# ESP32.net
KiCad netlist of a schematic drawn in Altium Designer
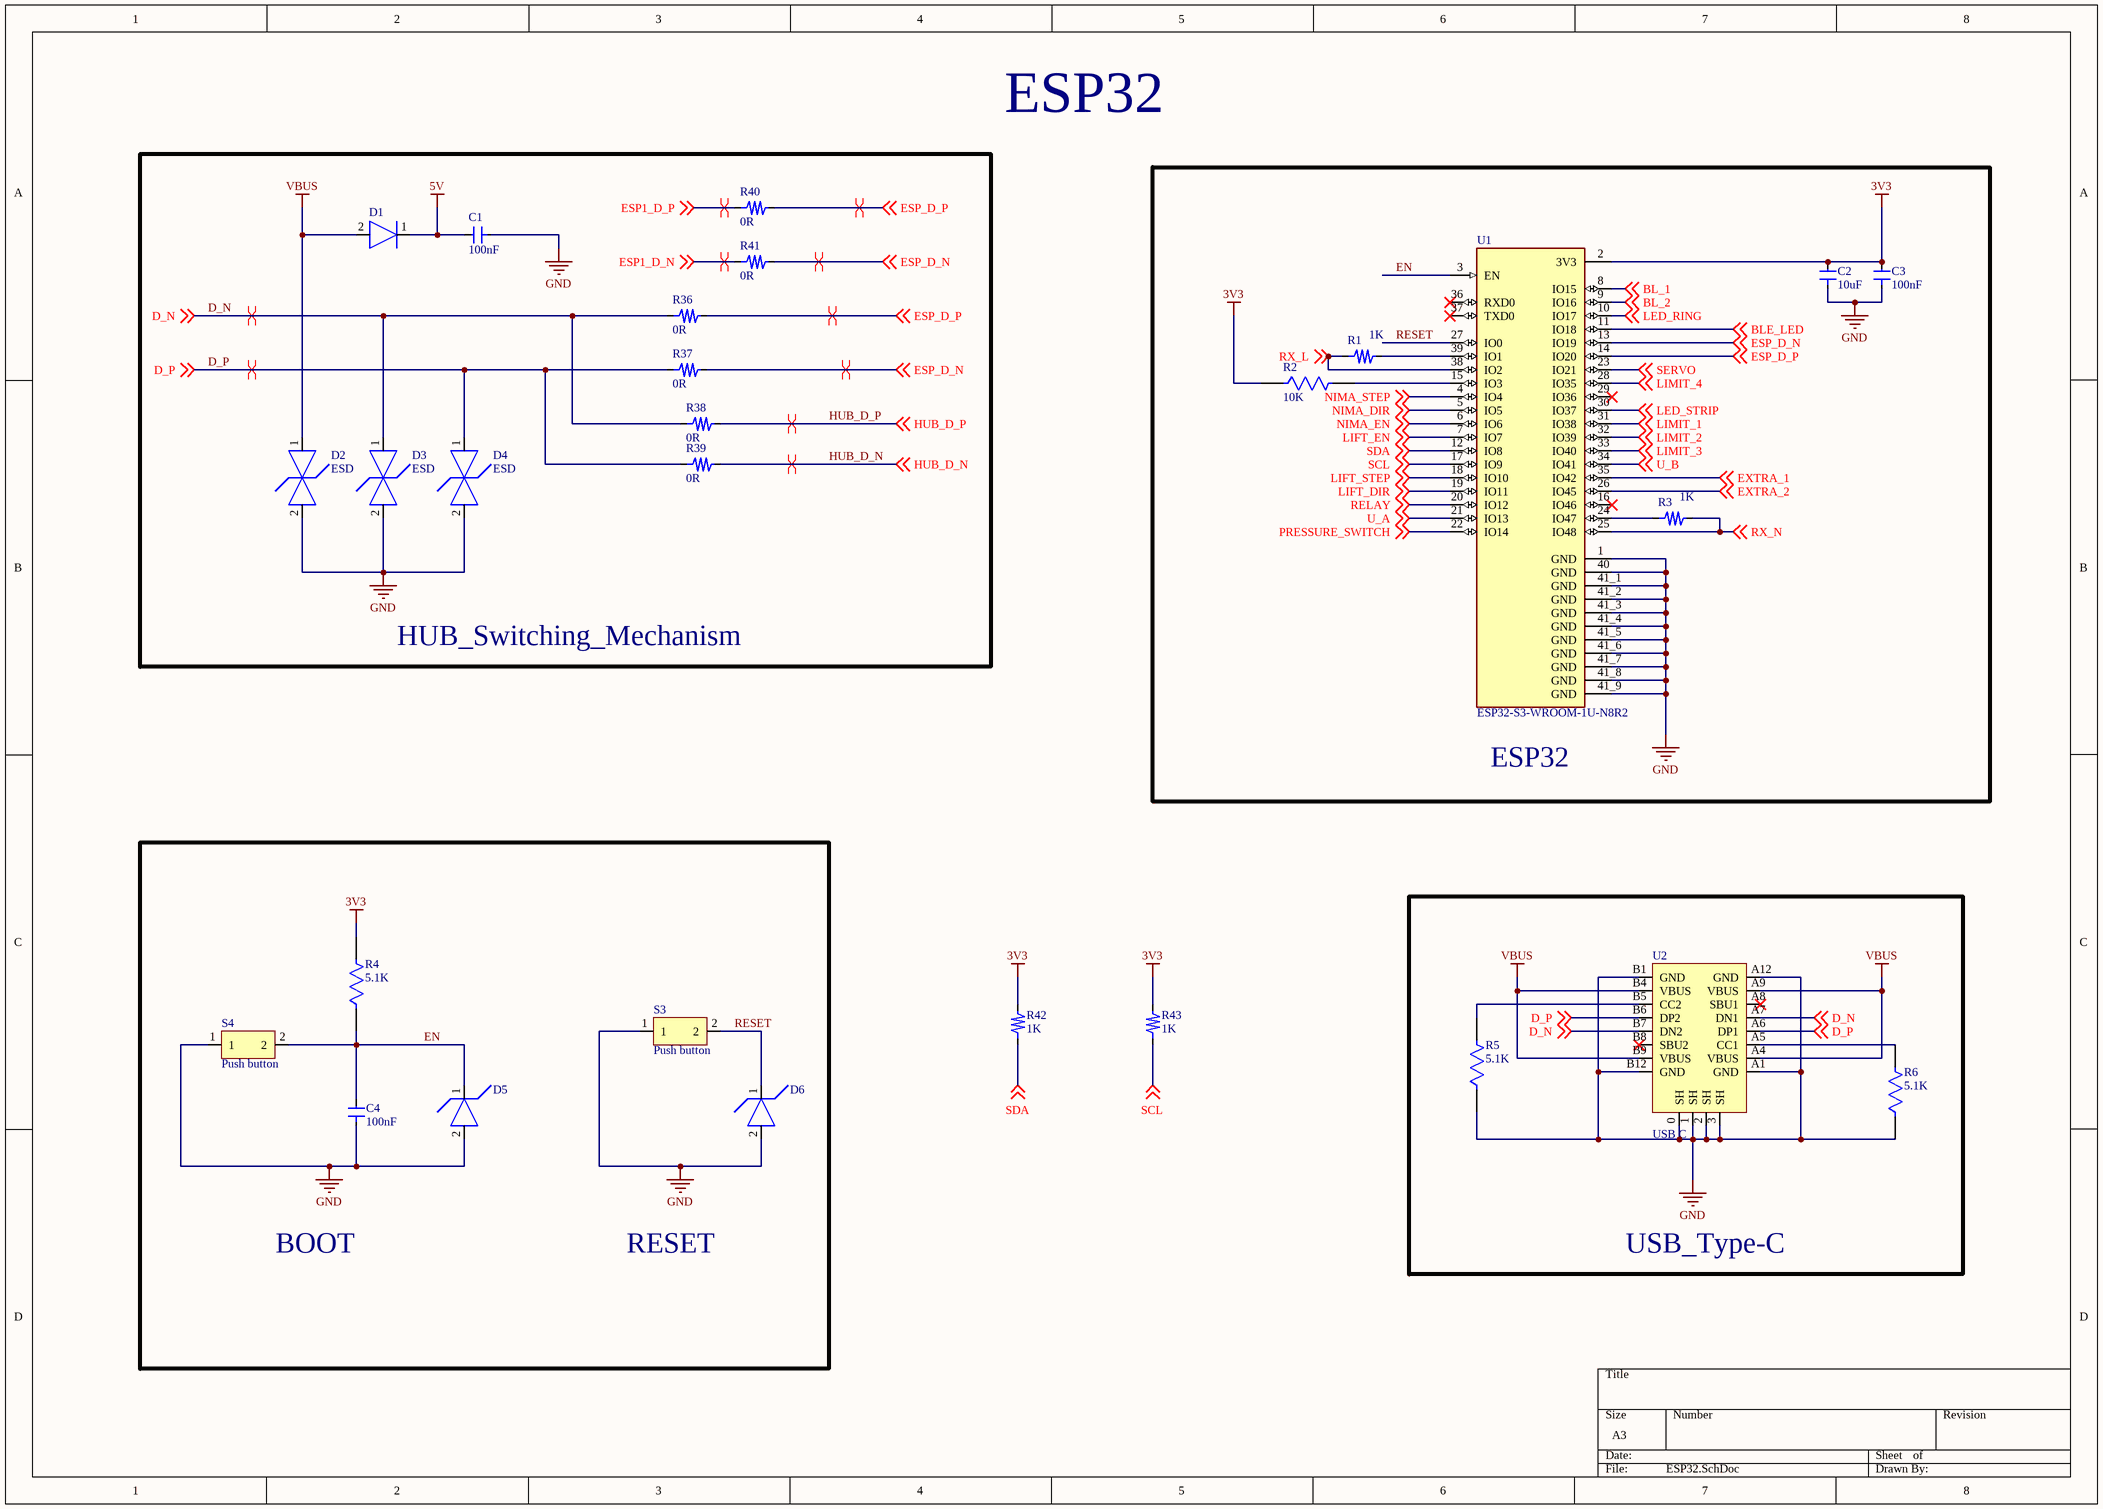
[diagram p0: ESP32.SchDoc]

(export (version "E")
  (design (tool "Eeschema 10.0.6"))
  (components
    (comp (ref "C1")
      (value "100nF")
      (footprint "CAP 0603")
      (fields (field (name "PART NUMBER") "CC0603JRX7R9BB104"))
      (libsource (lib "Schlib2") (part "Capasitor"))
    )
    (comp (ref "C2")
      (value "10uF")
      (footprint "CAP 0603")
      (fields (field (name "PART NUMBER") "CC0603KRX5R5BB106"))
      (libsource (lib "Schlib2") (part "Capasitor"))
    )
    (comp (ref "C3")
      (value "100nF")
      (footprint "CAP 0603")
      (fields (field (name "PART NUMBER") "CC0603JRX7R9BB104"))
      (libsource (lib "Schlib2") (part "Capasitor"))
    )
    (comp (ref "C4")
      (value "100nF")
      (footprint "CAP 0603")
      (fields (field (name "PART NUMBER") "CC0603JRX7R9BB104"))
      (libsource (lib "Schlib2") (part "Capasitor"))
    )
    (comp (ref "D1")
      (value "Diode")
      (footprint "Dioad")
      (fields (field (name "PART NUMBER") "1N5819WS"))
      (libsource (lib "Schlib2") (part "Diode"))
    )
    (comp (ref "D2")
      (value "ESD")
      (footprint "ESD")
      (fields (field (name "PART NUMBER") "LESD5D5.0CT1G(UMW)"))
      (libsource (lib "Schlib2") (part "ESD"))
    )
    (comp (ref "D3")
      (value "ESD")
      (footprint "ESD")
      (fields (field (name "PART NUMBER") "LESD5D5.0CT1G(UMW)"))
      (libsource (lib "Schlib2") (part "ESD"))
    )
    (comp (ref "D4")
      (value "ESD")
      (footprint "ESD")
      (fields (field (name "PART NUMBER") "LESD5D5.0CT1G(UMW)"))
      (libsource (lib "Schlib2") (part "ESD"))
    )
    (comp (ref "D5")
      (value "SINGAL ESD")
      (footprint "Singal ESD")
      (fields (field (name "PART NUMBER") "ESD5Z3.3T1G"))
      (libsource (lib "Schlib2") (part "SINGAL ESD"))
    )
    (comp (ref "D6")
      (value "SINGAL ESD")
      (footprint "Singal ESD")
      (fields (field (name "PART NUMBER") "ESD5Z3.3T1G"))
      (libsource (lib "Schlib2") (part "SINGAL ESD"))
    )
    (comp (ref "R1")
      (value "1K")
      (footprint "RES 0603")
      (fields (field (name "PART NUMBER") "AECR0603F1K00K9"))
      (libsource (lib "Schlib2") (part "Resistor"))
    )
    (comp (ref "R2")
      (value "10K")
      (footprint "RES 0603")
      (fields (field (name "PART NUMBER") "RC0603JR-0710KL"))
      (libsource (lib "Schlib2") (part "R NEW"))
    )
    (comp (ref "R3")
      (value "1K")
      (footprint "RES 0603")
      (fields (field (name "PART NUMBER") "AECR0603F1K00K9"))
      (libsource (lib "Schlib2") (part "Resistor"))
    )
    (comp (ref "R4")
      (value "5.1K")
      (footprint "RES 0603")
      (fields (field (name "PART NUMBER") "RC0603JR-075K1L"))
      (libsource (lib "Schlib2") (part "R NEW"))
    )
    (comp (ref "R5")
      (value "5.1K")
      (footprint "RES 0603")
      (fields (field (name "PART NUMBER") "RC0603JR-075K1L"))
      (libsource (lib "Schlib2") (part "R NEW"))
    )
    (comp (ref "R6")
      (value "5.1K")
      (footprint "RES 0603")
      (fields (field (name "PART NUMBER") "RC0603JR-075K1L"))
      (libsource (lib "Schlib2") (part "R NEW"))
    )
    (comp (ref "R36")
      (value "0R")
      (footprint "RES_0201")
      (fields (field (name "PART NUMBER") "RC0201FR-070RL"))
      (libsource (lib "Schlib2") (part "Resistor"))
    )
    (comp (ref "R37")
      (value "0R")
      (footprint "RES_0201")
      (fields (field (name "PART NUMBER") "RC0201FR-070RL"))
      (libsource (lib "Schlib2") (part "Resistor"))
    )
    (comp (ref "R38")
      (value "0R")
      (footprint "RES_0201")
      (fields (field (name "PART NUMBER") "RC0201FR-070RL"))
      (libsource (lib "Schlib2") (part "Resistor"))
    )
    (comp (ref "R39")
      (value "0R")
      (footprint "RES_0201")
      (fields (field (name "PART NUMBER") "RC0201FR-070RL"))
      (libsource (lib "Schlib2") (part "Resistor"))
    )
    (comp (ref "R40")
      (value "0R")
      (footprint "RES_0201")
      (fields (field (name "PART NUMBER") "RC0201FR-070RL"))
      (libsource (lib "Schlib2") (part "Resistor"))
    )
    (comp (ref "R41")
      (value "0R")
      (footprint "RES_0201")
      (fields (field (name "PART NUMBER") "RC0201FR-070RL"))
      (libsource (lib "Schlib2") (part "Resistor"))
    )
    (comp (ref "R42")
      (value "1K")
      (footprint "RES 0603")
      (fields (field (name "PART NUMBER") "RC0603FR-074K7L"))
      (libsource (lib "Schlib2") (part "Resistor"))
    )
    (comp (ref "R43")
      (value "1K")
      (footprint "RES 0603")
      (fields (field (name "PART NUMBER") "RC0603FR-074K7L"))
      (libsource (lib "Schlib2") (part "Resistor"))
    )
    (comp (ref "S3")
      (value "Push button")
      (footprint "Tactical Switch")
      (fields (field (name "PART NUMBER") "GT-TC060A-H025-L1S"))
      (libsource (lib "Schlib2") (part "Push button"))
    )
    (comp (ref "S4")
      (value "Push button")
      (footprint "Tactical Switch")
      (fields (field (name "PART NUMBER") "GT-TC060A-H025-L1S"))
      (libsource (lib "Schlib2") (part "Push button"))
    )
    (comp (ref "U1")
      (value "ESP32-S3-WROOM-1U-N8R2")
      (footprint "XCVR_ESP32-S3-WROOM-1U-N8R2")
      (libsource (lib "Schlib2") (part "ESP32-S3-WROOM-1U-N8R2"))
    )
    (comp (ref "U2")
      (value "USB C")
      (footprint "TYPE-C")
      (fields (field (name "PART NUMBER") "USB-TYPE-C-018"))
      (libsource (lib "Schlib2") (part "USB C"))
    )
  )
  (nets
    (net (code "1") (name "/EN") (class "Default")
      (node (ref "C4") (pin "2") (pinfunction "2_2") (pintype "passive"))
      (node (ref "D5") (pin "1") (pinfunction "1_1") (pintype "passive"))
      (node (ref "R4") (pin "1") (pinfunction "1_1") (pintype "passive"))
      (node (ref "S4") (pin "2") (pinfunction "2_2") (pintype "passive"))
      (node (ref "U1") (pin "3") (pinfunction "EN_3") (pintype "input"))
    )
    (net (code "2") (name "/RESET") (class "Default")
      (node (ref "D6") (pin "1") (pinfunction "1_1") (pintype "passive"))
      (node (ref "S3") (pin "2") (pinfunction "2_2") (pintype "passive"))
      (node (ref "U1") (pin "27") (pinfunction "IO0_27") (pintype "bidirectional"))
    )
    (net (code "3") (name "3V3") (class "Default")
      (node (ref "C2") (pin "2") (pinfunction "2_2") (pintype "passive"))
      (node (ref "C3") (pin "2") (pinfunction "2_2") (pintype "passive"))
      (node (ref "R2") (pin "1") (pinfunction "1_1") (pintype "passive"))
      (node (ref "R4") (pin "2") (pinfunction "2_2") (pintype "passive"))
      (node (ref "R42") (pin "2") (pinfunction "2_2") (pintype "passive"))
      (node (ref "R43") (pin "2") (pinfunction "2_2") (pintype "passive"))
      (node (ref "U1") (pin "2") (pinfunction "3V3_2") (pintype "passive"))
    )
    (net (code "4") (name "5V") (class "Default")
      (node (ref "C1") (pin "2") (pinfunction "2_2") (pintype "passive"))
      (node (ref "D1") (pin "1") (pinfunction "1_1") (pintype "passive"))
    )
    (net (code "5") (name "BLE_LED") (class "Default")
      (node (ref "U1") (pin "11") (pinfunction "IO18_11") (pintype "bidirectional"))
    )
    (net (code "6") (name "BL_1") (class "Default")
      (node (ref "U1") (pin "8") (pinfunction "IO15_8") (pintype "bidirectional"))
    )
    (net (code "7") (name "BL_2") (class "Default")
      (node (ref "U1") (pin "9") (pinfunction "IO16_9") (pintype "bidirectional"))
    )
    (net (code "8") (name "D_N") (class "Default")
      (node (ref "D3") (pin "1") (pinfunction "1_1") (pintype "passive"))
      (node (ref "R36") (pin "1") (pinfunction "1_1") (pintype "passive"))
      (node (ref "R38") (pin "1") (pinfunction "1_1") (pintype "passive"))
      (node (ref "U2") (pin "A7") (pinfunction "DN1_A7") (pintype "passive"))
      (node (ref "U2") (pin "B7") (pinfunction "DN2_B7") (pintype "passive"))
    )
    (net (code "9") (name "D_P") (class "Default")
      (node (ref "D4") (pin "1") (pinfunction "1_1") (pintype "passive"))
      (node (ref "R37") (pin "1") (pinfunction "1_1") (pintype "passive"))
      (node (ref "R39") (pin "1") (pinfunction "1_1") (pintype "passive"))
      (node (ref "U2") (pin "A6") (pinfunction "DP1_A6") (pintype "passive"))
      (node (ref "U2") (pin "B6") (pinfunction "DP2_B6") (pintype "passive"))
    )
    (net (code "10") (name "ESP1_D_N") (class "Default")
      (node (ref "R41") (pin "1") (pinfunction "1_1") (pintype "passive"))
    )
    (net (code "11") (name "ESP1_D_P") (class "Default")
      (node (ref "R40") (pin "1") (pinfunction "1_1") (pintype "passive"))
    )
    (net (code "12") (name "ESP_D_N") (class "Default")
      (node (ref "R37") (pin "2") (pinfunction "2_2") (pintype "passive"))
      (node (ref "R41") (pin "2") (pinfunction "2_2") (pintype "passive"))
      (node (ref "U1") (pin "13") (pinfunction "IO19_13") (pintype "bidirectional"))
    )
    (net (code "13") (name "ESP_D_P") (class "Default")
      (node (ref "R36") (pin "2") (pinfunction "2_2") (pintype "passive"))
      (node (ref "R40") (pin "2") (pinfunction "2_2") (pintype "passive"))
      (node (ref "U1") (pin "14") (pinfunction "IO20_14") (pintype "bidirectional"))
    )
    (net (code "14") (name "EXTRA_1") (class "Default")
      (node (ref "U1") (pin "35") (pinfunction "IO42_35") (pintype "bidirectional"))
    )
    (net (code "15") (name "EXTRA_2") (class "Default")
      (node (ref "U1") (pin "26") (pinfunction "IO45_26") (pintype "bidirectional"))
    )
    (net (code "16") (name "GND") (class "Default")
      (node (ref "C1") (pin "1") (pinfunction "1_1") (pintype "passive"))
      (node (ref "C2") (pin "1") (pinfunction "1_1") (pintype "passive"))
      (node (ref "C3") (pin "1") (pinfunction "1_1") (pintype "passive"))
      (node (ref "C4") (pin "1") (pinfunction "1_1") (pintype "passive"))
      (node (ref "D2") (pin "2") (pinfunction "2_2") (pintype "passive"))
      (node (ref "D3") (pin "2") (pinfunction "2_2") (pintype "passive"))
      (node (ref "D4") (pin "2") (pinfunction "2_2") (pintype "passive"))
      (node (ref "D5") (pin "2") (pinfunction "2_2") (pintype "passive"))
      (node (ref "D6") (pin "2") (pinfunction "2_2") (pintype "passive"))
      (node (ref "R5") (pin "1") (pinfunction "1_1") (pintype "passive"))
      (node (ref "R6") (pin "1") (pinfunction "1_1") (pintype "passive"))
      (node (ref "S3") (pin "1") (pinfunction "1_1") (pintype "passive"))
      (node (ref "S4") (pin "1") (pinfunction "1_1") (pintype "passive"))
      (node (ref "U1") (pin "1") (pinfunction "GND_1") (pintype "passive"))
      (node (ref "U1") (pin "40") (pinfunction "GND_40") (pintype "passive"))
      (node (ref "U1") (pin "41_1") (pinfunction "GND_41_1") (pintype "passive"))
      (node (ref "U1") (pin "41_2") (pinfunction "GND_41_2") (pintype "passive"))
      (node (ref "U1") (pin "41_3") (pinfunction "GND_41_3") (pintype "passive"))
      (node (ref "U1") (pin "41_4") (pinfunction "GND_41_4") (pintype "passive"))
      (node (ref "U1") (pin "41_5") (pinfunction "GND_41_5") (pintype "passive"))
      (node (ref "U1") (pin "41_6") (pinfunction "GND_41_6") (pintype "passive"))
      (node (ref "U1") (pin "41_7") (pinfunction "GND_41_7") (pintype "passive"))
      (node (ref "U1") (pin "41_8") (pinfunction "GND_41_8") (pintype "passive"))
      (node (ref "U1") (pin "41_9") (pinfunction "GND_41_9") (pintype "passive"))
      (node (ref "U2") (pin "0") (pinfunction "SH_0") (pintype "passive"))
      (node (ref "U2") (pin "1") (pinfunction "SH_1") (pintype "passive"))
      (node (ref "U2") (pin "2") (pinfunction "SH_2") (pintype "passive"))
      (node (ref "U2") (pin "3") (pinfunction "SH_3") (pintype "passive"))
      (node (ref "U2") (pin "A1") (pinfunction "GND_A1") (pintype "passive"))
      (node (ref "U2") (pin "A12") (pinfunction "GND_A12") (pintype "passive"))
      (node (ref "U2") (pin "B1") (pinfunction "GND_B1") (pintype "passive"))
      (node (ref "U2") (pin "B12") (pinfunction "GND_B12") (pintype "passive"))
    )
    (net (code "17") (name "HUB_D_N") (class "Default")
      (node (ref "R39") (pin "2") (pinfunction "2_2") (pintype "passive"))
    )
    (net (code "18") (name "HUB_D_P") (class "Default")
      (node (ref "R38") (pin "2") (pinfunction "2_2") (pintype "passive"))
    )
    (net (code "19") (name "LED_RING") (class "Default")
      (node (ref "U1") (pin "10") (pinfunction "IO17_10") (pintype "bidirectional"))
    )
    (net (code "20") (name "LED_STRIP") (class "Default")
      (node (ref "U1") (pin "30") (pinfunction "IO37_30") (pintype "bidirectional"))
    )
    (net (code "21") (name "LIFT_DIR") (class "Default")
      (node (ref "U1") (pin "19") (pinfunction "IO11_19") (pintype "bidirectional"))
    )
    (net (code "22") (name "LIFT_EN") (class "Default")
      (node (ref "U1") (pin "7") (pinfunction "IO7_7") (pintype "bidirectional"))
    )
    (net (code "23") (name "LIFT_STEP") (class "Default")
      (node (ref "U1") (pin "18") (pinfunction "IO10_18") (pintype "bidirectional"))
    )
    (net (code "24") (name "LIMIT_1") (class "Default")
      (node (ref "U1") (pin "31") (pinfunction "IO38_31") (pintype "bidirectional"))
    )
    (net (code "25") (name "LIMIT_2") (class "Default")
      (node (ref "U1") (pin "32") (pinfunction "IO39_32") (pintype "bidirectional"))
    )
    (net (code "26") (name "LIMIT_3") (class "Default")
      (node (ref "U1") (pin "33") (pinfunction "IO40_33") (pintype "bidirectional"))
    )
    (net (code "27") (name "LIMIT_4") (class "Default")
      (node (ref "U1") (pin "28") (pinfunction "IO35_28") (pintype "bidirectional"))
    )
    (net (code "28") (name "NIMA_DIR") (class "Default")
      (node (ref "U1") (pin "5") (pinfunction "IO5_5") (pintype "bidirectional"))
    )
    (net (code "29") (name "NIMA_EN") (class "Default")
      (node (ref "U1") (pin "6") (pinfunction "IO6_6") (pintype "bidirectional"))
    )
    (net (code "30") (name "NIMA_STEP") (class "Default")
      (node (ref "U1") (pin "4") (pinfunction "IO4_4") (pintype "bidirectional"))
    )
    (net (code "31") (name "Net-(U1-IO1)") (class "Default")
      (node (ref "R1") (pin "2") (pinfunction "2_2") (pintype "passive"))
      (node (ref "U1") (pin "39") (pinfunction "IO1_39") (pintype "bidirectional"))
    )
    (net (code "32") (name "Net-(U1-IO3)") (class "Default")
      (node (ref "R2") (pin "2") (pinfunction "2_2") (pintype "passive"))
      (node (ref "U1") (pin "15") (pinfunction "IO3_15") (pintype "bidirectional"))
    )
    (net (code "33") (name "Net-(U1-IO47)") (class "Default")
      (node (ref "R3") (pin "1") (pinfunction "1_1") (pintype "passive"))
      (node (ref "U1") (pin "24") (pinfunction "IO47_24") (pintype "bidirectional"))
    )
    (net (code "34") (name "Net-(U2-CC1)") (class "Default")
      (node (ref "R6") (pin "2") (pinfunction "2_2") (pintype "passive"))
      (node (ref "U2") (pin "A5") (pinfunction "CC1_A5") (pintype "passive"))
    )
    (net (code "35") (name "Net-(U2-CC2)") (class "Default")
      (node (ref "R5") (pin "2") (pinfunction "2_2") (pintype "passive"))
      (node (ref "U2") (pin "B5") (pinfunction "CC2_B5") (pintype "passive"))
    )
    (net (code "36") (name "PRESSURE_SWITCH") (class "Default")
      (node (ref "U1") (pin "22") (pinfunction "IO14_22") (pintype "bidirectional"))
    )
    (net (code "37") (name "RELAY") (class "Default")
      (node (ref "U1") (pin "20") (pinfunction "IO12_20") (pintype "bidirectional"))
    )
    (net (code "38") (name "RX_L") (class "Default")
      (node (ref "R1") (pin "1") (pinfunction "1_1") (pintype "passive"))
      (node (ref "U1") (pin "38") (pinfunction "IO2_38") (pintype "bidirectional"))
    )
    (net (code "39") (name "RX_N") (class "Default")
      (node (ref "R3") (pin "2") (pinfunction "2_2") (pintype "passive"))
      (node (ref "U1") (pin "25") (pinfunction "IO48_25") (pintype "bidirectional"))
    )
    (net (code "40") (name "SCL") (class "Default")
      (node (ref "R43") (pin "1") (pinfunction "1_1") (pintype "passive"))
      (node (ref "U1") (pin "17") (pinfunction "IO9_17") (pintype "bidirectional"))
    )
    (net (code "41") (name "SDA") (class "Default")
      (node (ref "R42") (pin "1") (pinfunction "1_1") (pintype "passive"))
      (node (ref "U1") (pin "12") (pinfunction "IO8_12") (pintype "bidirectional"))
    )
    (net (code "42") (name "SERVO") (class "Default")
      (node (ref "U1") (pin "23") (pinfunction "IO21_23") (pintype "bidirectional"))
    )
    (net (code "43") (name "U_A") (class "Default")
      (node (ref "U1") (pin "21") (pinfunction "IO13_21") (pintype "bidirectional"))
    )
    (net (code "44") (name "U_B") (class "Default")
      (node (ref "U1") (pin "34") (pinfunction "IO41_34") (pintype "bidirectional"))
    )
    (net (code "45") (name "VBUS") (class "Default")
      (node (ref "D1") (pin "2") (pinfunction "2_2") (pintype "passive"))
      (node (ref "D2") (pin "1") (pinfunction "1_1") (pintype "passive"))
      (node (ref "U2") (pin "A4") (pinfunction "VBUS_A4") (pintype "passive"))
      (node (ref "U2") (pin "A9") (pinfunction "VBUS_A9") (pintype "passive"))
      (node (ref "U2") (pin "B4") (pinfunction "VBUS_B4") (pintype "passive"))
      (node (ref "U2") (pin "B9") (pinfunction "VBUS_B9") (pintype "passive"))
    )
    (net (code "46") (name "unconnected-(U1-IO36-Pad29)") (class "Default")
      (node (ref "U1") (pin "29") (pinfunction "IO36_29") (pintype "bidirectional+no_connect"))
    )
    (net (code "47") (name "unconnected-(U1-IO46-Pad16)") (class "Default")
      (node (ref "U1") (pin "16") (pinfunction "IO46_16") (pintype "bidirectional+no_connect"))
    )
    (net (code "48") (name "unconnected-(U1-RXD0-Pad36)") (class "Default")
      (node (ref "U1") (pin "36") (pinfunction "RXD0_36") (pintype "bidirectional+no_connect"))
    )
    (net (code "49") (name "unconnected-(U1-TXD0-Pad37)") (class "Default")
      (node (ref "U1") (pin "37") (pinfunction "TXD0_37") (pintype "bidirectional+no_connect"))
    )
    (net (code "50") (name "unconnected-(U2-SBU1-PadA8)") (class "Default")
      (node (ref "U2") (pin "A8") (pinfunction "SBU1_A8") (pintype "passive+no_connect"))
    )
    (net (code "51") (name "unconnected-(U2-SBU2-PadB8)") (class "Default")
      (node (ref "U2") (pin "B8") (pinfunction "SBU2_B8") (pintype "passive+no_connect"))
    )
  )
)
